# IV51.net
KiCad netlist of a schematic drawn in EAGLE
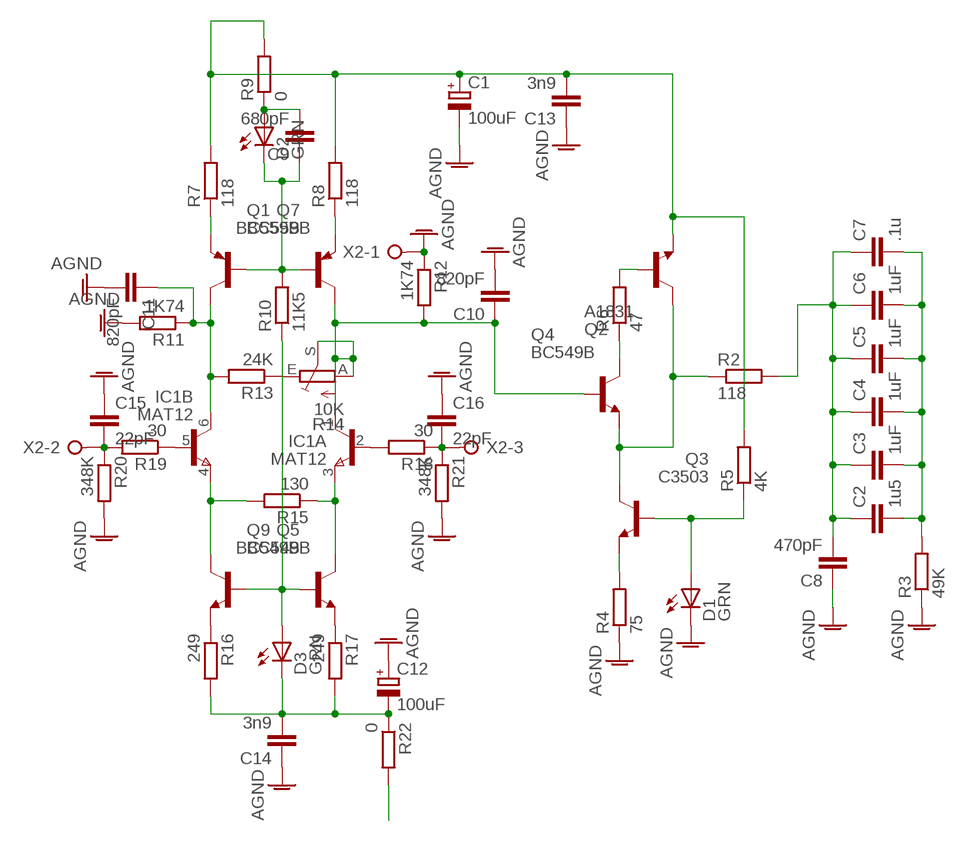
[diagram p0: schematic, sheet 1]

(export (version "E")
  (design (tool "Eeschema 10.0.6"))
  (components
    (comp (ref "C1")
      (value "100uF")
      (footprint "eagle-import:E5-10,5")
      (libsource (lib "eagle-import") (part "CPOL-EUE5-10.5"))
    )
    (comp (ref "C2")
      (value "1u5")
      (footprint "eagle-import:C275-134X316")
      (libsource (lib "eagle-import") (part "C-EU275-134X316"))
    )
    (comp (ref "C3")
      (value "1uF")
      (footprint "eagle-import:C275-134X316")
      (libsource (lib "eagle-import") (part "C-EU275-134X316"))
    )
    (comp (ref "C4")
      (value "1uF")
      (footprint "eagle-import:C275-134X316")
      (libsource (lib "eagle-import") (part "C-EU275-134X316"))
    )
    (comp (ref "C5")
      (value "1uF")
      (footprint "eagle-import:C275-134X316")
      (libsource (lib "eagle-import") (part "C-EU275-134X316"))
    )
    (comp (ref "C6")
      (value "1uF")
      (footprint "eagle-import:C275-134X316")
      (libsource (lib "eagle-import") (part "C-EU275-134X316"))
    )
    (comp (ref "C7")
      (value ".1u")
      (footprint "eagle-import:C050-075X075")
      (libsource (lib "eagle-import") (part "C-EU050-075X075"))
    )
    (comp (ref "C8")
      (value "470pF")
      (footprint "eagle-import:C102-043X133")
      (libsource (lib "eagle-import") (part "C-EU102-043X133"))
    )
    (comp (ref "C9")
      (value "680pF")
      (footprint "eagle-import:C050-045X075")
      (libsource (lib "eagle-import") (part "C-EU050-045X075"))
    )
    (comp (ref "C10")
      (value "820pF")
      (footprint "eagle-import:C075-032X103")
      (libsource (lib "eagle-import") (part "C-EU075-032X103"))
    )
    (comp (ref "C11")
      (value "820pF")
      (footprint "eagle-import:C075-032X103")
      (libsource (lib "eagle-import") (part "C-EU075-032X103"))
    )
    (comp (ref "C12")
      (value "100uF")
      (footprint "eagle-import:E5-10,5")
      (libsource (lib "eagle-import") (part "CPOL-EUE5-10.5"))
    )
    (comp (ref "C13")
      (value "3n9")
      (footprint "eagle-import:C1210")
      (libsource (lib "eagle-import") (part "C-EUC1210"))
    )
    (comp (ref "C14")
      (value "3n9")
      (footprint "eagle-import:C1210")
      (libsource (lib "eagle-import") (part "C-EUC1210"))
    )
    (comp (ref "C15")
      (value "22pF")
      (footprint "eagle-import:C075-032X103")
      (libsource (lib "eagle-import") (part "C-EU075-032X103"))
    )
    (comp (ref "C16")
      (value "22pF")
      (footprint "eagle-import:C075-032X103")
      (libsource (lib "eagle-import") (part "C-EU075-032X103"))
    )
    (comp (ref "D1")
      (value "GRN")
      (footprint "eagle-import:SFH482")
      (libsource (lib "eagle-import") (part "SFH482"))
    )
    (comp (ref "D2")
      (value "GRN")
      (footprint "eagle-import:SFH482")
      (libsource (lib "eagle-import") (part "SFH482"))
    )
    (comp (ref "D3")
      (value "GRN")
      (footprint "eagle-import:SFH482")
      (libsource (lib "eagle-import") (part "SFH482"))
    )
    (comp (ref "IC1")
      (value "MAT12")
      (footprint "eagle-import:TO78")
      (libsource (lib "eagle-import") (part "MAT-02H"))
    )
    (comp (ref "Q1")
      (value "BC559B")
      (footprint "eagle-import:TO92-EBC")
      (libsource (lib "eagle-import") (part "BC559A"))
    )
    (comp (ref "Q2")
      (value "A1831")
      (footprint "eagle-import:TO126")
      (libsource (lib "eagle-import") (part "2N4923"))
    )
    (comp (ref "Q3")
      (value "C3503")
      (footprint "eagle-import:TO126")
      (libsource (lib "eagle-import") (part "2N4923"))
    )
    (comp (ref "Q4")
      (value "BC549B")
      (footprint "eagle-import:TO92-EBC")
      (libsource (lib "eagle-import") (part "BC549B"))
    )
    (comp (ref "Q5")
      (value "BC549B")
      (footprint "eagle-import:TO92-EBC")
      (libsource (lib "eagle-import") (part "BC549B"))
    )
    (comp (ref "Q7")
      (value "BC559B")
      (footprint "eagle-import:TO92-EBC")
      (libsource (lib "eagle-import") (part "BC559A"))
    )
    (comp (ref "Q9")
      (value "BC549B")
      (footprint "eagle-import:TO92-EBC")
      (libsource (lib "eagle-import") (part "BC549B"))
    )
    (comp (ref "R2")
      (value "118")
      (footprint "eagle-import:0309_12")
      (libsource (lib "eagle-import") (part "R-EU_0309/12"))
    )
    (comp (ref "R3")
      (value "49K")
      (footprint "eagle-import:0309_12")
      (libsource (lib "eagle-import") (part "R-EU_0309/12"))
    )
    (comp (ref "R4")
      (value "75")
      (footprint "eagle-import:0309_12")
      (libsource (lib "eagle-import") (part "R-EU_0309/12"))
    )
    (comp (ref "R5")
      (value "4K")
      (footprint "eagle-import:0309_12")
      (libsource (lib "eagle-import") (part "R-EU_0309/12"))
    )
    (comp (ref "R6")
      (value "47")
      (footprint "eagle-import:0309_12")
      (libsource (lib "eagle-import") (part "R-EU_0309/12"))
    )
    (comp (ref "R7")
      (value "118")
      (footprint "eagle-import:0309_12")
      (libsource (lib "eagle-import") (part "R-EU_0309/12"))
    )
    (comp (ref "R8")
      (value "118")
      (footprint "eagle-import:0309_12")
      (libsource (lib "eagle-import") (part "R-EU_0309/12"))
    )
    (comp (ref "R9")
      (value "0")
      (footprint "eagle-import:0309_12")
      (libsource (lib "eagle-import") (part "R-EU_0309/12"))
    )
    (comp (ref "R10")
      (value "11K5")
      (footprint "eagle-import:0309_12")
      (libsource (lib "eagle-import") (part "R-EU_0309/12"))
    )
    (comp (ref "R11")
      (value "1K74")
      (footprint "eagle-import:0309_12")
      (libsource (lib "eagle-import") (part "R-EU_0309/12"))
    )
    (comp (ref "R12")
      (value "1K74")
      (footprint "eagle-import:0309_12")
      (libsource (lib "eagle-import") (part "R-EU_0309/12"))
    )
    (comp (ref "R13")
      (value "24K")
      (footprint "eagle-import:0309_12")
      (libsource (lib "eagle-import") (part "R-EU_0309/12"))
    )
    (comp (ref "R14")
      (value "10K")
      (footprint "eagle-import:RJ9W")
      (libsource (lib "eagle-import") (part "TRIM_EU-RJ9W"))
    )
    (comp (ref "R15")
      (value "130")
      (footprint "eagle-import:0309_12")
      (libsource (lib "eagle-import") (part "R-EU_0309/12"))
    )
    (comp (ref "R16")
      (value "249")
      (footprint "eagle-import:R2010")
      (libsource (lib "eagle-import") (part "R-EU_R2010"))
    )
    (comp (ref "R17")
      (value "249")
      (footprint "eagle-import:R2010")
      (libsource (lib "eagle-import") (part "R-EU_R2010"))
    )
    (comp (ref "R18")
      (value "30")
      (footprint "eagle-import:0309_12")
      (libsource (lib "eagle-import") (part "R-EU_0309/12"))
    )
    (comp (ref "R19")
      (value "30")
      (footprint "eagle-import:0309_12")
      (libsource (lib "eagle-import") (part "R-EU_0309/12"))
    )
    (comp (ref "R20")
      (value "348K")
      (footprint "eagle-import:R1210")
      (libsource (lib "eagle-import") (part "R-EU_R1210"))
    )
    (comp (ref "R21")
      (value "348K")
      (footprint "eagle-import:R1210")
      (libsource (lib "eagle-import") (part "R-EU_R1210"))
    )
    (comp (ref "R22")
      (value "0")
      (footprint "eagle-import:0309_12")
      (libsource (lib "eagle-import") (part "R-EU_0309/12"))
    )
    (comp (ref "X2")
      (value "W237-3E")
      (footprint "eagle-import:W237-3E")
      (libsource (lib "eagle-import") (part "W237-3E"))
    )
  )
  (nets
    (net (code "1") (name "AGND") (class "Default")
      (node (ref "C1") (pin "-") (pinfunction "-_-") (pintype "passive"))
      (node (ref "C10") (pin "2") (pinfunction "2_2") (pintype "passive"))
      (node (ref "C11") (pin "2") (pinfunction "2_2") (pintype "passive"))
      (node (ref "C12") (pin "+") (pinfunction "+_+") (pintype "passive"))
      (node (ref "C13") (pin "1") (pinfunction "1_1") (pintype "passive"))
      (node (ref "C14") (pin "1") (pinfunction "1_1") (pintype "passive"))
      (node (ref "C15") (pin "1") (pinfunction "1_1") (pintype "passive"))
      (node (ref "C16") (pin "1") (pinfunction "1_1") (pintype "passive"))
      (node (ref "C8") (pin "1") (pinfunction "1_1") (pintype "passive"))
      (node (ref "D1") (pin "K") (pinfunction "C_K") (pintype "passive"))
      (node (ref "R11") (pin "2") (pinfunction "2_2") (pintype "passive"))
      (node (ref "R12") (pin "1") (pinfunction "1_1") (pintype "passive"))
      (node (ref "R20") (pin "2") (pinfunction "2_2") (pintype "passive"))
      (node (ref "R21") (pin "2") (pinfunction "2_2") (pintype "passive"))
      (node (ref "R3") (pin "1") (pinfunction "1_1") (pintype "passive"))
      (node (ref "R4") (pin "1") (pinfunction "1_1") (pintype "passive"))
      (node (ref "X2") (pin "1") (pinfunction "KL_1") (pintype "passive"))
    )
    (net (code "2") (name "Net-(C2-Pad1)") (class "Default")
      (node (ref "C2") (pin "1") (pinfunction "1_1") (pintype "passive"))
      (node (ref "C3") (pin "1") (pinfunction "1_1") (pintype "passive"))
      (node (ref "C4") (pin "1") (pinfunction "1_1") (pintype "passive"))
      (node (ref "C5") (pin "1") (pinfunction "1_1") (pintype "passive"))
      (node (ref "C6") (pin "1") (pinfunction "1_1") (pintype "passive"))
      (node (ref "C7") (pin "1") (pinfunction "1_1") (pintype "passive"))
      (node (ref "C8") (pin "2") (pinfunction "2_2") (pintype "passive"))
      (node (ref "R2") (pin "2") (pinfunction "2_2") (pintype "passive"))
    )
    (net (code "3") (name "Net-(C2-Pad2)") (class "Default")
      (node (ref "C2") (pin "2") (pinfunction "2_2") (pintype "passive"))
      (node (ref "C3") (pin "2") (pinfunction "2_2") (pintype "passive"))
      (node (ref "C4") (pin "2") (pinfunction "2_2") (pintype "passive"))
      (node (ref "C5") (pin "2") (pinfunction "2_2") (pintype "passive"))
      (node (ref "C6") (pin "2") (pinfunction "2_2") (pintype "passive"))
      (node (ref "C7") (pin "2") (pinfunction "2_2") (pintype "passive"))
      (node (ref "R3") (pin "2") (pinfunction "2_2") (pintype "passive"))
    )
    (net (code "4") (name "Net-(C9-Pad2)") (class "Default")
      (node (ref "C9") (pin "2") (pinfunction "2_2") (pintype "passive"))
      (node (ref "D2") (pin "A") (pinfunction "A_A") (pintype "passive"))
      (node (ref "R9") (pin "1") (pinfunction "1_1") (pintype "passive"))
    )
    (net (code "5") (name "Net-(D2-C)") (class "Default")
      (node (ref "C9") (pin "1") (pinfunction "1_1") (pintype "passive"))
      (node (ref "D2") (pin "K") (pinfunction "C_K") (pintype "passive"))
      (node (ref "Q1") (pin "B") (pinfunction "B_B") (pintype "passive"))
      (node (ref "Q7") (pin "B") (pinfunction "B_B") (pintype "passive"))
      (node (ref "R10") (pin "2") (pinfunction "2_2") (pintype "passive"))
    )
    (net (code "6") (name "Net-(D3-C)") (class "Default")
      (node (ref "C12") (pin "-") (pinfunction "-_-") (pintype "passive"))
      (node (ref "C14") (pin "2") (pinfunction "2_2") (pintype "passive"))
      (node (ref "D3") (pin "K") (pinfunction "C_K") (pintype "passive"))
      (node (ref "R16") (pin "2") (pinfunction "2_2") (pintype "passive"))
      (node (ref "R17") (pin "2") (pinfunction "2_2") (pintype "passive"))
      (node (ref "R22") (pin "1") (pinfunction "1_1") (pintype "passive"))
    )
    (net (code "7") (name "Net-(D3-PadA)") (class "Default")
      (node (ref "D3") (pin "A") (pinfunction "A_A") (pintype "passive"))
      (node (ref "Q5") (pin "B") (pinfunction "B_B") (pintype "passive"))
      (node (ref "Q9") (pin "B") (pinfunction "B_B") (pintype "passive"))
      (node (ref "R10") (pin "1") (pinfunction "1_1") (pintype "passive"))
    )
    (net (code "8") (name "Net-(IC1A-B)") (class "Default")
      (node (ref "IC1") (pin "2") (pinfunction "B_2") (pintype "passive"))
      (node (ref "R18") (pin "2") (pinfunction "2_2") (pintype "passive"))
    )
    (net (code "9") (name "Net-(IC1A-C)") (class "Default")
      (node (ref "C10") (pin "1") (pinfunction "1_1") (pintype "passive"))
      (node (ref "IC1") (pin "1") (pinfunction "C_1") (pintype "passive"))
      (node (ref "Q1") (pin "C") (pinfunction "C_C") (pintype "passive"))
      (node (ref "Q4") (pin "B") (pinfunction "B_B") (pintype "passive"))
      (node (ref "R12") (pin "2") (pinfunction "2_2") (pintype "passive"))
      (node (ref "R14") (pin "A") (pinfunction "A_A") (pintype "passive"))
      (node (ref "R14") (pin "S") (pinfunction "S_S") (pintype "passive"))
    )
    (net (code "10") (name "Net-(IC1A-E)") (class "Default")
      (node (ref "IC1") (pin "3") (pinfunction "E_3") (pintype "passive"))
      (node (ref "Q9") (pin "C") (pinfunction "C_C") (pintype "passive"))
      (node (ref "R15") (pin "1") (pinfunction "1_1") (pintype "passive"))
    )
    (net (code "11") (name "Net-(IC1B-B)") (class "Default")
      (node (ref "IC1") (pin "5") (pinfunction "B_5") (pintype "passive"))
      (node (ref "R19") (pin "1") (pinfunction "1_1") (pintype "passive"))
    )
    (net (code "12") (name "Net-(IC1B-C)") (class "Default")
      (node (ref "C11") (pin "1") (pinfunction "1_1") (pintype "passive"))
      (node (ref "IC1") (pin "6") (pinfunction "C_6") (pintype "passive"))
      (node (ref "Q7") (pin "C") (pinfunction "C_C") (pintype "passive"))
      (node (ref "R11") (pin "1") (pinfunction "1_1") (pintype "passive"))
      (node (ref "R13") (pin "2") (pinfunction "2_2") (pintype "passive"))
    )
    (net (code "13") (name "Net-(IC1B-E)") (class "Default")
      (node (ref "IC1") (pin "4") (pinfunction "E_4") (pintype "passive"))
      (node (ref "Q5") (pin "C") (pinfunction "C_C") (pintype "passive"))
      (node (ref "R15") (pin "2") (pinfunction "2_2") (pintype "passive"))
    )
    (net (code "14") (name "Net-(Q1-PadE)") (class "Default")
      (node (ref "Q1") (pin "E") (pinfunction "E_E") (pintype "passive"))
      (node (ref "R8") (pin "1") (pinfunction "1_1") (pintype "passive"))
    )
    (net (code "15") (name "Net-(Q2-B)") (class "Default")
      (node (ref "Q2") (pin "3") (pinfunction "B_3") (pintype "passive"))
      (node (ref "R6") (pin "2") (pinfunction "2_2") (pintype "passive"))
    )
    (net (code "16") (name "Net-(Q2-C)") (class "Default")
      (node (ref "Q2") (pin "2") (pinfunction "C_2") (pintype "passive"))
      (node (ref "Q3") (pin "2") (pinfunction "C_2") (pintype "passive"))
      (node (ref "Q4") (pin "E") (pinfunction "E_E") (pintype "passive"))
      (node (ref "R2") (pin "1") (pinfunction "1_1") (pintype "passive"))
    )
    (net (code "17") (name "Net-(Q2-E)") (class "Default")
      (node (ref "C1") (pin "+") (pinfunction "+_+") (pintype "passive"))
      (node (ref "C13") (pin "2") (pinfunction "2_2") (pintype "passive"))
      (node (ref "Q2") (pin "1") (pinfunction "E_1") (pintype "passive"))
      (node (ref "R5") (pin "2") (pinfunction "2_2") (pintype "passive"))
      (node (ref "R7") (pin "2") (pinfunction "2_2") (pintype "passive"))
      (node (ref "R8") (pin "2") (pinfunction "2_2") (pintype "passive"))
      (node (ref "R9") (pin "2") (pinfunction "2_2") (pintype "passive"))
    )
    (net (code "18") (name "Net-(Q3-B)") (class "Default")
      (node (ref "D1") (pin "A") (pinfunction "A_A") (pintype "passive"))
      (node (ref "Q3") (pin "3") (pinfunction "B_3") (pintype "passive"))
      (node (ref "R5") (pin "1") (pinfunction "1_1") (pintype "passive"))
    )
    (net (code "19") (name "Net-(Q3-E)") (class "Default")
      (node (ref "Q3") (pin "1") (pinfunction "E_1") (pintype "passive"))
      (node (ref "R4") (pin "2") (pinfunction "2_2") (pintype "passive"))
    )
    (net (code "20") (name "Net-(Q4-PadC)") (class "Default")
      (node (ref "Q4") (pin "C") (pinfunction "C_C") (pintype "passive"))
      (node (ref "R6") (pin "1") (pinfunction "1_1") (pintype "passive"))
    )
    (net (code "21") (name "Net-(Q5-PadE)") (class "Default")
      (node (ref "Q5") (pin "E") (pinfunction "E_E") (pintype "passive"))
      (node (ref "R16") (pin "1") (pinfunction "1_1") (pintype "passive"))
    )
    (net (code "22") (name "Net-(Q7-PadE)") (class "Default")
      (node (ref "Q7") (pin "E") (pinfunction "E_E") (pintype "passive"))
      (node (ref "R7") (pin "1") (pinfunction "1_1") (pintype "passive"))
    )
    (net (code "23") (name "Net-(Q9-PadE)") (class "Default")
      (node (ref "Q9") (pin "E") (pinfunction "E_E") (pintype "passive"))
      (node (ref "R17") (pin "1") (pinfunction "1_1") (pintype "passive"))
    )
    (net (code "24") (name "Net-(R13-Pad1)") (class "Default")
      (node (ref "R13") (pin "1") (pinfunction "1_1") (pintype "passive"))
      (node (ref "R14") (pin "E") (pinfunction "E_E") (pintype "passive"))
    )
    (net (code "25") (name "Net-(X2B-KL)") (class "Default")
      (node (ref "C15") (pin "2") (pinfunction "2_2") (pintype "passive"))
      (node (ref "R19") (pin "2") (pinfunction "2_2") (pintype "passive"))
      (node (ref "R20") (pin "1") (pinfunction "1_1") (pintype "passive"))
      (node (ref "X2") (pin "2") (pinfunction "KL_2") (pintype "passive"))
    )
    (net (code "26") (name "Net-(X2C-KL)") (class "Default")
      (node (ref "C16") (pin "2") (pinfunction "2_2") (pintype "passive"))
      (node (ref "R18") (pin "1") (pinfunction "1_1") (pintype "passive"))
      (node (ref "R21") (pin "1") (pinfunction "1_1") (pintype "passive"))
      (node (ref "X2") (pin "3") (pinfunction "KL_3") (pintype "passive"))
    )
    (net (code "27") (name "unconnected-(R22-Pad2)") (class "Default")
      (node (ref "R22") (pin "2") (pinfunction "2_2") (pintype "passive"))
    )
  )
)
